# usbB_isp.net
KiCad netlist of a schematic drawn in EAGLE
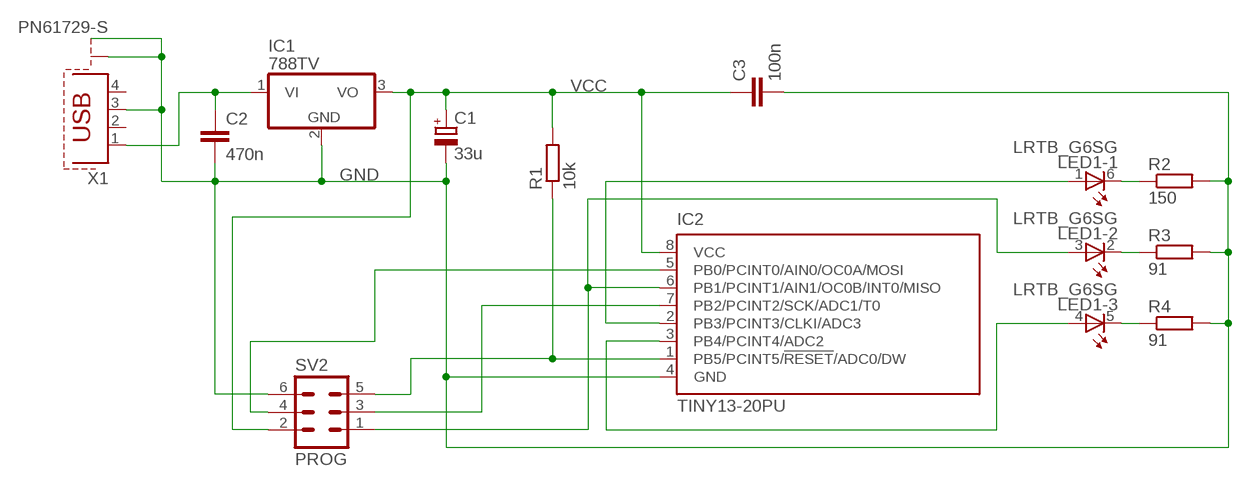
[diagram p0: schematic, sheet 1]

(export (version "E")
  (design (tool "Eeschema 10.0.6"))
  (components
    (comp (ref "C1")
      (value "33u")
      (footprint "eagle-import:E2,5-6E")
      (libsource (lib "eagle-import") (part "CPOL-EUE2,5-6E"))
    )
    (comp (ref "C2")
      (value "470n")
      (footprint "eagle-import:C050-025X075")
      (libsource (lib "eagle-import") (part "C-EU050-025X075"))
    )
    (comp (ref "C3")
      (value "100n")
      (footprint "eagle-import:C050-025X075")
      (libsource (lib "eagle-import") (part "C-EU050-025X075"))
    )
    (comp (ref "IC1")
      (value "788TV")
      (footprint "eagle-import:TO220V")
      (libsource (lib "eagle-import") (part "78TV8"))
    )
    (comp (ref "IC2")
      (value "TINY13-20PU")
      (footprint "eagle-import:DIL08")
      (fields (field (name "MPN") "ATTINY13-20PU"))
      (libsource (lib "eagle-import") (part "TINY13PU-20"))
    )
    (comp (ref "LED1")
      (value "LRTB_G6SG")
      (footprint "eagle-import:LRTB_G6SG")
      (libsource (lib "eagle-import") (part "LRTB_G6SG"))
    )
    (comp (ref "R1")
      (value "10k")
      (footprint "eagle-import:0204_7")
      (libsource (lib "eagle-import") (part "R-EU_0204/7"))
    )
    (comp (ref "R2")
      (value "150")
      (footprint "eagle-import:0204_7")
      (libsource (lib "eagle-import") (part "R-EU_0204/7"))
    )
    (comp (ref "R3")
      (value "91")
      (footprint "eagle-import:0204_7")
      (libsource (lib "eagle-import") (part "R-EU_0204/7"))
    )
    (comp (ref "R4")
      (value "91")
      (footprint "eagle-import:0204_7")
      (libsource (lib "eagle-import") (part "R-EU_0204/7"))
    )
    (comp (ref "SV2")
      (value "PROG")
      (footprint "eagle-import:ML6")
      (libsource (lib "eagle-import") (part "ML6"))
    )
    (comp (ref "X1")
      (value "PN61729-S")
      (footprint "eagle-import:PN61729-S")
      (libsource (lib "eagle-import") (part "PN61729-S"))
    )
  )
  (nets
    (net (code "1") (name "/GND") (class "Default")
      (node (ref "C1") (pin "-") (pinfunction "-_-") (pintype "passive"))
      (node (ref "C2") (pin "2") (pinfunction "2_2") (pintype "passive"))
      (node (ref "C3") (pin "2") (pinfunction "2_2") (pintype "passive"))
      (node (ref "IC1") (pin "2") (pinfunction "GND_2") (pintype "passive"))
      (node (ref "IC2") (pin "4") (pinfunction "GND_4") (pintype "power_in"))
      (node (ref "R2") (pin "2") (pinfunction "2_2") (pintype "passive"))
      (node (ref "R3") (pin "2") (pinfunction "2_2") (pintype "passive"))
      (node (ref "R4") (pin "2") (pinfunction "2_2") (pintype "passive"))
      (node (ref "SV2") (pin "6") (pinfunction "6_6") (pintype "passive"))
      (node (ref "X1") (pin "3") (pinfunction "3_3") (pintype "passive"))
      (node (ref "X1") (pin "S1") (pinfunction "S1_S1") (pintype "passive"))
    )
    (net (code "2") (name "/VCC") (class "Default")
      (node (ref "C1") (pin "+") (pinfunction "+_+") (pintype "passive"))
      (node (ref "C3") (pin "1") (pinfunction "1_1") (pintype "passive"))
      (node (ref "IC1") (pin "3") (pinfunction "VO_3") (pintype "passive"))
      (node (ref "IC2") (pin "8") (pinfunction "VCC_8") (pintype "power_in"))
      (node (ref "R1") (pin "2") (pinfunction "2_2") (pintype "passive"))
      (node (ref "SV2") (pin "2") (pinfunction "2_2") (pintype "passive"))
    )
    (net (code "3") (name "Net-(IC1-VI)") (class "Default")
      (node (ref "C2") (pin "1") (pinfunction "1_1") (pintype "passive"))
      (node (ref "IC1") (pin "1") (pinfunction "VI_1") (pintype "input"))
      (node (ref "X1") (pin "1") (pinfunction "1_1") (pintype "passive"))
    )
    (net (code "4") (name "Net-(IC2-PB0{slash}PCINT0{slash}AIN0{slash}OC0A{slash}MOSI)") (class "Default")
      (node (ref "IC2") (pin "5") (pinfunction "PB0/PCINT0/AIN0/OC0A/MOSI_5") (pintype "bidirectional"))
      (node (ref "SV2") (pin "4") (pinfunction "4_4") (pintype "passive"))
    )
    (net (code "5") (name "Net-(IC2-PB1{slash}PCINT1{slash}AIN1{slash}OC0B{slash}INT0{slash}MISO)") (class "Default")
      (node (ref "IC2") (pin "6") (pinfunction "PB1/PCINT1/AIN1/OC0B/INT0/MISO_6") (pintype "bidirectional"))
      (node (ref "LED1") (pin "3") (pinfunction "A_3") (pintype "passive"))
      (node (ref "SV2") (pin "1") (pinfunction "1_1") (pintype "passive"))
    )
    (net (code "6") (name "Net-(IC2-PB2{slash}PCINT2{slash}SCK{slash}ADC1{slash}T0)") (class "Default")
      (node (ref "IC2") (pin "7") (pinfunction "PB2/PCINT2/SCK/ADC1/T0_7") (pintype "bidirectional"))
      (node (ref "SV2") (pin "3") (pinfunction "3_3") (pintype "passive"))
    )
    (net (code "7") (name "Net-(IC2-PB3{slash}PCINT3{slash}CLKI{slash}ADC3)") (class "Default")
      (node (ref "IC2") (pin "2") (pinfunction "PB3/PCINT3/CLKI/ADC3_2") (pintype "bidirectional"))
      (node (ref "LED1") (pin "1") (pinfunction "A_1") (pintype "passive"))
    )
    (net (code "8") (name "Net-(IC2-PB4{slash}PCINT4{slash}ADC2)") (class "Default")
      (node (ref "IC2") (pin "3") (pinfunction "PB4/PCINT4/ADC2_3") (pintype "bidirectional"))
      (node (ref "LED1") (pin "4") (pinfunction "A_4") (pintype "passive"))
    )
    (net (code "9") (name "Net-(IC2-PB5{slash}PCINT5{slash}~{RESET}{slash}ADC0{slash}DW)") (class "Default")
      (node (ref "IC2") (pin "1") (pinfunction "PB5/PCINT5/~{RESET}/ADC0/DW_1") (pintype "bidirectional"))
      (node (ref "R1") (pin "1") (pinfunction "1_1") (pintype "passive"))
      (node (ref "SV2") (pin "5") (pinfunction "5_5") (pintype "passive"))
    )
    (net (code "10") (name "Net-(LED1A-C)") (class "Default")
      (node (ref "LED1") (pin "6") (pinfunction "C_6") (pintype "passive"))
      (node (ref "R2") (pin "1") (pinfunction "1_1") (pintype "passive"))
    )
    (net (code "11") (name "Net-(LED1B-C)") (class "Default")
      (node (ref "LED1") (pin "2") (pinfunction "C_2") (pintype "passive"))
      (node (ref "R3") (pin "1") (pinfunction "1_1") (pintype "passive"))
    )
    (net (code "12") (name "Net-(LED1C-C)") (class "Default")
      (node (ref "LED1") (pin "5") (pinfunction "C_5") (pintype "passive"))
      (node (ref "R4") (pin "1") (pinfunction "1_1") (pintype "passive"))
    )
    (net (code "13") (name "unconnected-(X1-Pad2)") (class "Default")
      (node (ref "X1") (pin "2") (pinfunction "2_2") (pintype "passive"))
    )
    (net (code "14") (name "unconnected-(X1-Pad4)") (class "Default")
      (node (ref "X1") (pin "4") (pinfunction "4_4") (pintype "passive"))
    )
    (net (code "15") (name "unconnected-(X1-PadS2)") (class "Default")
      (node (ref "X1") (pin "S2") (pinfunction "S2_S2") (pintype "passive"))
    )
  )
)
